# VIA_MOTORS.net
KiCad netlist of a schematic drawn in Altium Designer
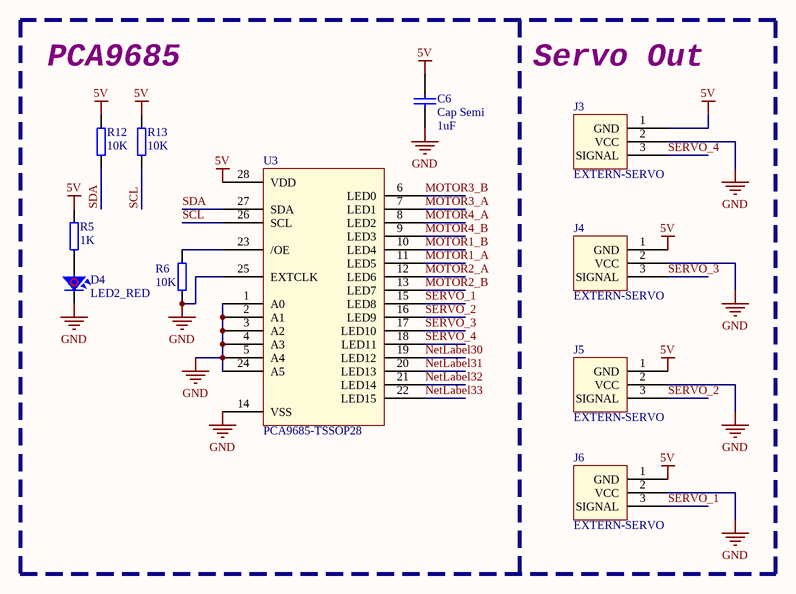
[diagram p0: VIA_MOTORS.SchDoc]

(export (version "E")
  (design (tool "Eeschema 10.0.6"))
  (components
    (comp (ref "C6")
      (value "Cap Semi")
      (footprint "SMT0603")
      (description "CAP SM 0603 X7R 1uF 10%")
      (fields (field (name "TOLERANCE") "±10%") (field (name "ALTIUM_VALUE") "1uF"))
      (libsource (lib "electronpowered") (part "CAP-SM-0603-X7R-1uF"))
    )
    (comp (ref "D4")
      (value "LED2_RED")
      (footprint "LED_RED_SMD0603")
      (description "LED RED CLEAR 0603 SMD")
      (fields
        (field (name "MANUFACTURER") "Lite-On Inc.")
        (field (name "MANUFACTURER PART NUMBER") "LTST-C191KRKT")
      )
      (libsource (lib "RASHBERRY_EXTERN") (part "LED2_RED-0603/200mA-2V"))
    )
    (comp (ref "J3")
      (value "EXTERN-SERVO")
      (footprint "JP3H")
      (libsource (lib "RASHBERRY_EXTERN") (part "EXTERN-SERVO"))
    )
    (comp (ref "J4")
      (value "EXTERN-SERVO")
      (footprint "JP3H")
      (libsource (lib "RASHBERRY_EXTERN") (part "EXTERN-SERVO"))
    )
    (comp (ref "J5")
      (value "EXTERN-SERVO")
      (footprint "JP3H")
      (libsource (lib "RASHBERRY_EXTERN") (part "EXTERN-SERVO"))
    )
    (comp (ref "J6")
      (value "EXTERN-SERVO")
      (footprint "JP3H")
      (libsource (lib "RASHBERRY_EXTERN") (part "EXTERN-SERVO"))
    )
    (comp (ref "R5")
      (value "1K")
      (footprint "SMT0603")
      (description "RES SM 0603 1K")
      (fields (field (name "Comment") "Resistor"))
      (libsource (lib "electronpowered") (part "RES-SM-0603-1K"))
    )
    (comp (ref "R6")
      (value "10K")
      (footprint "SMT0603")
      (description "RES SM 0603 10K")
      (fields (field (name "Comment") "Resistor"))
      (libsource (lib "electronpowered") (part "RES-SM-0603-10K"))
    )
    (comp (ref "R12")
      (value "10K")
      (footprint "SMT0603")
      (description "RES SM 0603 10K")
      (fields (field (name "Comment") "Resistor"))
      (libsource (lib "electronpowered") (part "RES-SM-0603-10K"))
    )
    (comp (ref "R13")
      (value "10K")
      (footprint "SMT0603")
      (description "RES SM 0603 10K")
      (fields (field (name "Comment") "Resistor"))
      (libsource (lib "electronpowered") (part "RES-SM-0603-10K"))
    )
    (comp (ref "U3")
      (value "PCA9685-TSSOP28")
      (footprint "TSSOP28-SMD")
      (libsource (lib "RASHBERRY_EXTERN") (part "PCA9685-TSSOP28"))
    )
  )
  (nets
    (net (code "1") (name "/MOTOR1_A") (class "Default")
      (node (ref "U3") (pin "11") (pinfunction "LED5_11") (pintype "passive"))
    )
    (net (code "2") (name "/MOTOR1_B") (class "Default")
      (node (ref "U3") (pin "10") (pinfunction "LED4_10") (pintype "passive"))
    )
    (net (code "3") (name "/MOTOR2_A") (class "Default")
      (node (ref "U3") (pin "12") (pinfunction "LED6_12") (pintype "passive"))
    )
    (net (code "4") (name "/MOTOR2_B") (class "Default")
      (node (ref "U3") (pin "13") (pinfunction "LED7_13") (pintype "passive"))
    )
    (net (code "5") (name "/MOTOR3_A") (class "Default")
      (node (ref "U3") (pin "7") (pinfunction "LED1_7") (pintype "passive"))
    )
    (net (code "6") (name "/MOTOR3_B") (class "Default")
      (node (ref "U3") (pin "6") (pinfunction "LED0_6") (pintype "passive"))
    )
    (net (code "7") (name "/MOTOR4_A") (class "Default")
      (node (ref "U3") (pin "8") (pinfunction "LED2_8") (pintype "passive"))
    )
    (net (code "8") (name "/MOTOR4_B") (class "Default")
      (node (ref "U3") (pin "9") (pinfunction "LED3_9") (pintype "passive"))
    )
    (net (code "9") (name "/NetLabel30") (class "Default")
      (node (ref "U3") (pin "19") (pinfunction "LED12_19") (pintype "passive"))
    )
    (net (code "10") (name "/NetLabel31") (class "Default")
      (node (ref "U3") (pin "20") (pinfunction "LED13_20") (pintype "passive"))
    )
    (net (code "11") (name "/NetLabel32") (class "Default")
      (node (ref "U3") (pin "21") (pinfunction "LED14_21") (pintype "passive"))
    )
    (net (code "12") (name "/NetLabel33") (class "Default")
      (node (ref "U3") (pin "22") (pinfunction "LED15_22") (pintype "passive"))
    )
    (net (code "13") (name "/SCL") (class "Default")
      (node (ref "R13") (pin "1") (pinfunction "1_1") (pintype "passive"))
      (node (ref "U3") (pin "26") (pinfunction "SCL_26") (pintype "passive"))
    )
    (net (code "14") (name "/SDA") (class "Default")
      (node (ref "R12") (pin "1") (pinfunction "1_1") (pintype "passive"))
      (node (ref "U3") (pin "27") (pinfunction "SDA_27") (pintype "passive"))
    )
    (net (code "15") (name "/SERVO_1") (class "Default")
      (node (ref "J6") (pin "3") (pinfunction "SIGNAL_3") (pintype "passive"))
      (node (ref "U3") (pin "15") (pinfunction "LED8_15") (pintype "passive"))
    )
    (net (code "16") (name "/SERVO_2") (class "Default")
      (node (ref "J5") (pin "3") (pinfunction "SIGNAL_3") (pintype "passive"))
      (node (ref "U3") (pin "16") (pinfunction "LED9_16") (pintype "passive"))
    )
    (net (code "17") (name "/SERVO_3") (class "Default")
      (node (ref "J4") (pin "3") (pinfunction "SIGNAL_3") (pintype "passive"))
      (node (ref "U3") (pin "17") (pinfunction "LED10_17") (pintype "passive"))
    )
    (net (code "18") (name "/SERVO_4") (class "Default")
      (node (ref "J3") (pin "3") (pinfunction "SIGNAL_3") (pintype "passive"))
      (node (ref "U3") (pin "18") (pinfunction "LED11_18") (pintype "passive"))
    )
    (net (code "19") (name "5V") (class "Default")
      (node (ref "C6") (pin "2") (pinfunction "2_2") (pintype "passive"))
      (node (ref "J3") (pin "1") (pinfunction "GND_1") (pintype "passive"))
      (node (ref "J4") (pin "1") (pinfunction "GND_1") (pintype "passive"))
      (node (ref "J5") (pin "1") (pinfunction "GND_1") (pintype "passive"))
      (node (ref "J6") (pin "1") (pinfunction "GND_1") (pintype "passive"))
      (node (ref "R12") (pin "2") (pinfunction "2_2") (pintype "passive"))
      (node (ref "R13") (pin "2") (pinfunction "2_2") (pintype "passive"))
      (node (ref "R5") (pin "2") (pinfunction "2_2") (pintype "passive"))
      (node (ref "U3") (pin "28") (pinfunction "VDD_28") (pintype "passive"))
    )
    (net (code "20") (name "GND") (class "Default")
      (node (ref "C6") (pin "1") (pinfunction "1_1") (pintype "passive"))
      (node (ref "D4") (pin "2") (pinfunction "2_2") (pintype "passive"))
      (node (ref "J3") (pin "2") (pinfunction "VCC_2") (pintype "passive"))
      (node (ref "J4") (pin "2") (pinfunction "VCC_2") (pintype "passive"))
      (node (ref "J5") (pin "2") (pinfunction "VCC_2") (pintype "passive"))
      (node (ref "J6") (pin "2") (pinfunction "VCC_2") (pintype "passive"))
      (node (ref "R6") (pin "1") (pinfunction "1_1") (pintype "passive"))
      (node (ref "U3") (pin "1") (pinfunction "A0_1") (pintype "passive"))
      (node (ref "U3") (pin "14") (pinfunction "VSS_14") (pintype "passive"))
      (node (ref "U3") (pin "2") (pinfunction "A1_2") (pintype "passive"))
      (node (ref "U3") (pin "24") (pinfunction "A5_24") (pintype "passive"))
      (node (ref "U3") (pin "25") (pinfunction "EXTCLK_25") (pintype "passive"))
      (node (ref "U3") (pin "3") (pinfunction "A2_3") (pintype "passive"))
      (node (ref "U3") (pin "4") (pinfunction "A3_4") (pintype "passive"))
      (node (ref "U3") (pin "5") (pinfunction "A4_5") (pintype "passive"))
    )
    (net (code "21") (name "Net-(D4-Pad1)") (class "Default")
      (node (ref "D4") (pin "1") (pinfunction "1_1") (pintype "passive"))
      (node (ref "R5") (pin "1") (pinfunction "1_1") (pintype "passive"))
    )
    (net (code "22") (name "Net-(U3-{slash}OE)") (class "Default")
      (node (ref "R6") (pin "2") (pinfunction "2_2") (pintype "passive"))
      (node (ref "U3") (pin "23") (pinfunction "/OE_23") (pintype "passive"))
    )
  )
)
